# FPC_MAIN_TO_ES.net
KiCad netlist of a schematic drawn in Altium Designer
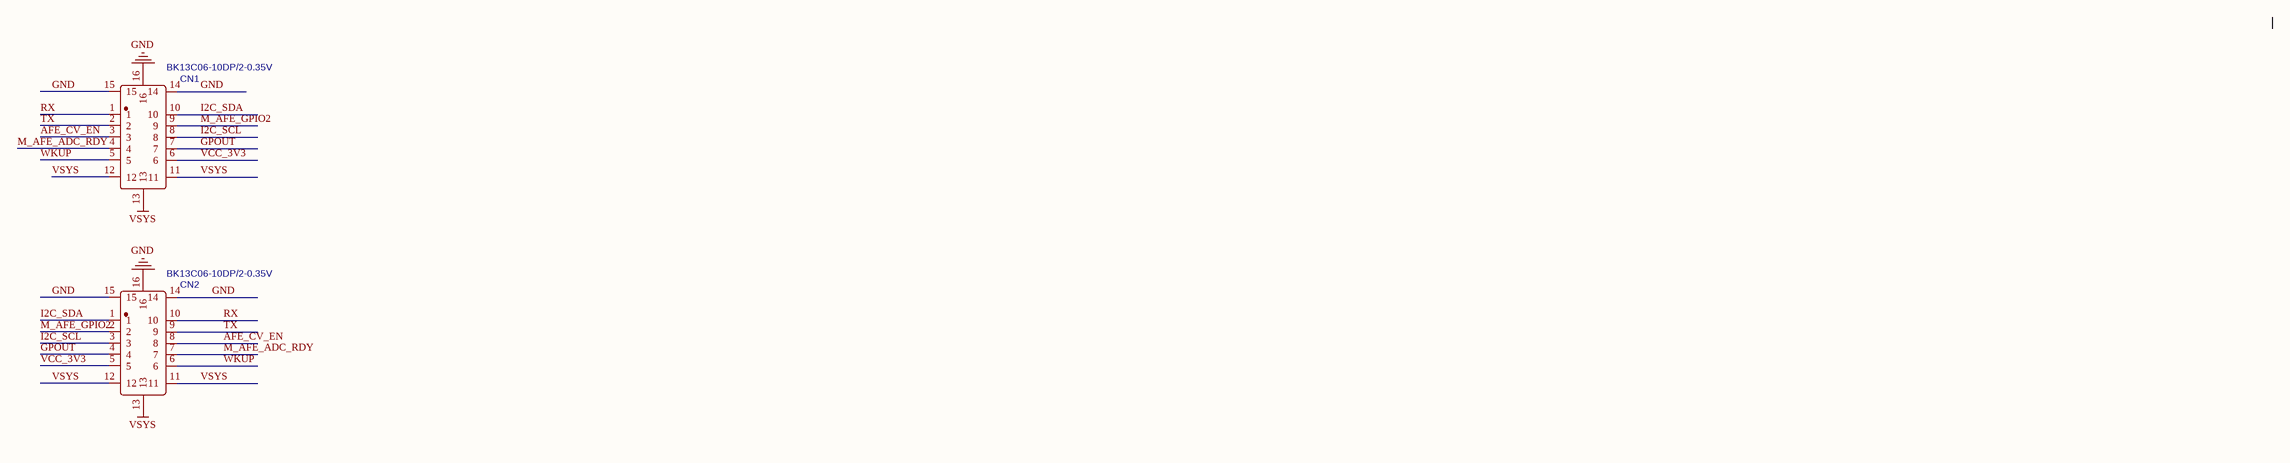
[diagram p0: FPC_MAIN_TO_ES.SchDoc]

(export (version "E")
  (design (tool "Eeschema 10.0.6"))
  (components
    (comp (ref "CN1")
      (value "BK13C06-10DP/2-0.35V")
      (footprint "smart bracelet:CONN-SMD_10P-P0.35_BK13C06-10DP")
      (fields (field (name "CONTRIBUTOR") "lcsc"))
      (libsource (lib "smart bracelet") (part "10pin_dp_BK13C06-10DP/2-0.35V"))
    )
    (comp (ref "CN2")
      (value "BK13C06-10DP/2-0.35V")
      (footprint "smart bracelet:CONN-SMD_10P-P0.35_BK13C06-10DP")
      (fields (field (name "CONTRIBUTOR") "lcsc"))
      (libsource (lib "smart bracelet") (part "10pin_dp_BK13C06-10DP/2-0.35V"))
    )
  )
  (nets
    (net (code "1") (name "/AFE_CV_EN") (class "Default")
      (node (ref "CN1") (pin "3") (pinfunction "3_3") (pintype "passive"))
      (node (ref "CN2") (pin "8") (pinfunction "8_8") (pintype "passive"))
    )
    (net (code "2") (name "/GPOUT") (class "Default")
      (node (ref "CN1") (pin "7") (pinfunction "7_7") (pintype "passive"))
      (node (ref "CN2") (pin "4") (pinfunction "4_4") (pintype "passive"))
    )
    (net (code "3") (name "/I2C_SCL") (class "Default")
      (node (ref "CN1") (pin "8") (pinfunction "8_8") (pintype "passive"))
      (node (ref "CN2") (pin "3") (pinfunction "3_3") (pintype "passive"))
    )
    (net (code "4") (name "/I2C_SDA") (class "Default")
      (node (ref "CN1") (pin "10") (pinfunction "10_10") (pintype "passive"))
      (node (ref "CN2") (pin "1") (pinfunction "1_1") (pintype "passive"))
    )
    (net (code "5") (name "/M_AFE_ADC_RDY") (class "Default")
      (node (ref "CN1") (pin "4") (pinfunction "4_4") (pintype "passive"))
      (node (ref "CN2") (pin "7") (pinfunction "7_7") (pintype "passive"))
    )
    (net (code "6") (name "/M_AFE_GPIO2") (class "Default")
      (node (ref "CN1") (pin "9") (pinfunction "9_9") (pintype "passive"))
      (node (ref "CN2") (pin "2") (pinfunction "2_2") (pintype "passive"))
    )
    (net (code "7") (name "/RX") (class "Default")
      (node (ref "CN1") (pin "1") (pinfunction "1_1") (pintype "passive"))
      (node (ref "CN2") (pin "10") (pinfunction "10_10") (pintype "passive"))
    )
    (net (code "8") (name "/TX") (class "Default")
      (node (ref "CN1") (pin "2") (pinfunction "2_2") (pintype "passive"))
      (node (ref "CN2") (pin "9") (pinfunction "9_9") (pintype "passive"))
    )
    (net (code "9") (name "/VCC_3V3") (class "Default")
      (node (ref "CN1") (pin "6") (pinfunction "6_6") (pintype "passive"))
      (node (ref "CN2") (pin "5") (pinfunction "5_5") (pintype "passive"))
    )
    (net (code "10") (name "/WKUP") (class "Default")
      (node (ref "CN1") (pin "5") (pinfunction "5_5") (pintype "passive"))
      (node (ref "CN2") (pin "6") (pinfunction "6_6") (pintype "passive"))
    )
    (net (code "11") (name "GND") (class "Default")
      (node (ref "CN1") (pin "14") (pinfunction "14_14") (pintype "passive"))
      (node (ref "CN1") (pin "15") (pinfunction "15_15") (pintype "passive"))
      (node (ref "CN1") (pin "16") (pinfunction "16_16") (pintype "passive"))
      (node (ref "CN2") (pin "14") (pinfunction "14_14") (pintype "passive"))
      (node (ref "CN2") (pin "15") (pinfunction "15_15") (pintype "passive"))
      (node (ref "CN2") (pin "16") (pinfunction "16_16") (pintype "passive"))
    )
    (net (code "12") (name "VSYS") (class "Default")
      (node (ref "CN1") (pin "11") (pinfunction "11_11") (pintype "passive"))
      (node (ref "CN1") (pin "12") (pinfunction "12_12") (pintype "passive"))
      (node (ref "CN1") (pin "13") (pinfunction "13_13") (pintype "passive"))
      (node (ref "CN2") (pin "11") (pinfunction "11_11") (pintype "passive"))
      (node (ref "CN2") (pin "12") (pinfunction "12_12") (pintype "passive"))
      (node (ref "CN2") (pin "13") (pinfunction "13_13") (pintype "passive"))
    )
  )
)
